# MCU.net
KiCad netlist of a schematic drawn in Altium Designer
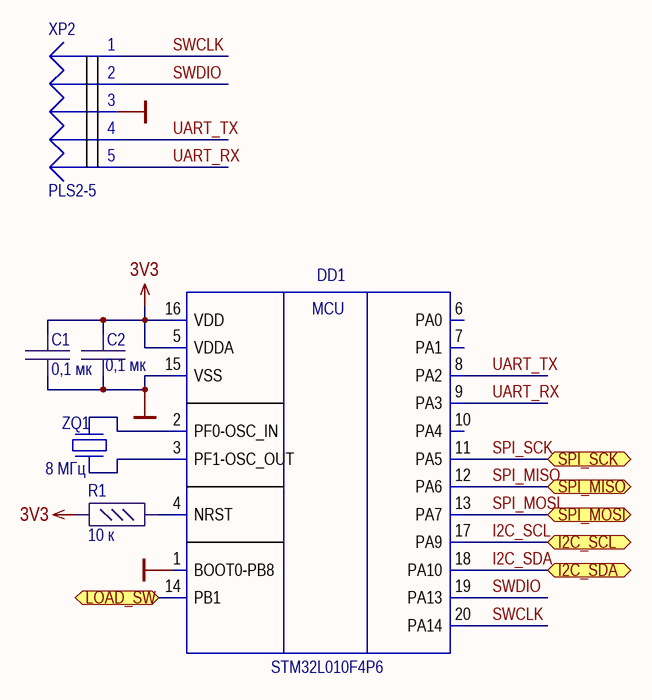
[diagram p0: MCU.SchDoc]

(export (version "E")
  (design (tool "Eeschema 10.0.6"))
  (components
    (comp (ref "C1")
      (value "0,1 мк")
      (footprint "C_0603")
      (description "CAP CER 0.1UF 100V X7R 0603")
      (fields
        (field (name "PART NUMBER") "GRM188R72A104MA35D")
        (field (name "MANUFACTURER") "Murata Electronics")
      )
      (libsource (lib "Database_Lib") (part "Capasitor"))
    )
    (comp (ref "C2")
      (value "0,1 мк")
      (footprint "C_0603")
      (description "CAP CER 0.1UF 100V X7R 0603")
      (fields
        (field (name "PART NUMBER") "GRM188R72A104MA35D")
        (field (name "MANUFACTURER") "Murata Electronics")
      )
      (libsource (lib "Database_Lib") (part "Capasitor"))
    )
    (comp (ref "DD1")
      (value "STM32L010F4P6")
      (footprint "TSSOP-20")
      (libsource (lib "6.Chips") (part "STM32L010F4P6"))
    )
    (comp (ref "R1")
      (value "10 к")
      (footprint "R_0603")
      (description "RES SMD 10K OHM 1% 1/10W 0603")
      (fields (field (name "PART NUMBER") "CR0603-FX-1002ELF") (field (name "MANUFACTURER") "Bourns Inc."))
      (libsource (lib "Database_Lib") (part "Resistor"))
    )
    (comp (ref "XP2") (value "PLS2-5") (footprint "PLS2-5") (libsource (lib "7.Connectors") (part "PLS2-5")))
    (comp (ref "ZQ1")
      (value "8 МГц")
      (footprint "MJ CRYSTAL")
      (libsource (lib "8.Resonarors") (part "NX5032GA-8MHz"))
    )
  )
  (nets
    (net (code "1") (name "/I2C_SCL") (class "Default")
      (node (ref "DD1") (pin "17") (pinfunction "PA9_17") (pintype "passive"))
    )
    (net (code "2") (name "/I2C_SDA") (class "Default")
      (node (ref "DD1") (pin "18") (pinfunction "PA10_18") (pintype "passive"))
    )
    (net (code "3") (name "/LOAD_SW") (class "Default")
      (node (ref "DD1") (pin "14") (pinfunction "PB1_14") (pintype "passive"))
    )
    (net (code "4") (name "/SPI_MISO") (class "Default")
      (node (ref "DD1") (pin "12") (pinfunction "PA6_12") (pintype "passive"))
    )
    (net (code "5") (name "/SPI_MOSI") (class "Default")
      (node (ref "DD1") (pin "13") (pinfunction "PA7_13") (pintype "passive"))
    )
    (net (code "6") (name "/SPI_SCK") (class "Default")
      (node (ref "DD1") (pin "11") (pinfunction "PA5_11") (pintype "passive"))
    )
    (net (code "7") (name "/SWCLK") (class "Default")
      (node (ref "DD1") (pin "20") (pinfunction "PA14_20") (pintype "passive"))
      (node (ref "XP2") (pin "1") (pinfunction "1_1") (pintype "passive"))
    )
    (net (code "8") (name "/SWDIO") (class "Default")
      (node (ref "DD1") (pin "19") (pinfunction "PA13_19") (pintype "passive"))
      (node (ref "XP2") (pin "2") (pinfunction "2_2") (pintype "passive"))
    )
    (net (code "9") (name "/UART_RX") (class "Default")
      (node (ref "DD1") (pin "9") (pinfunction "PA3_9") (pintype "passive"))
      (node (ref "XP2") (pin "5") (pinfunction "5_5") (pintype "passive"))
    )
    (net (code "10") (name "/UART_TX") (class "Default")
      (node (ref "DD1") (pin "8") (pinfunction "PA2_8") (pintype "passive"))
      (node (ref "XP2") (pin "4") (pinfunction "4_4") (pintype "passive"))
    )
    (net (code "11") (name "3V3") (class "Default")
      (node (ref "C1") (pin "2") (pinfunction "2_2") (pintype "passive"))
      (node (ref "C2") (pin "2") (pinfunction "2_2") (pintype "passive"))
      (node (ref "DD1") (pin "16") (pinfunction "VDD_16") (pintype "passive"))
      (node (ref "DD1") (pin "5") (pinfunction "VDDA_5") (pintype "passive"))
      (node (ref "R1") (pin "1") (pinfunction "1_1") (pintype "passive"))
    )
    (net (code "12") (name "GND") (class "Default")
      (node (ref "C1") (pin "1") (pinfunction "1_1") (pintype "passive"))
      (node (ref "C2") (pin "1") (pinfunction "1_1") (pintype "passive"))
      (node (ref "DD1") (pin "1") (pinfunction "BOOT0-PB8_1") (pintype "passive"))
      (node (ref "DD1") (pin "15") (pinfunction "VSS_15") (pintype "passive"))
      (node (ref "XP2") (pin "3") (pinfunction "3_3") (pintype "passive"))
    )
    (net (code "13") (name "Net-(DD1-NRST)") (class "Default")
      (node (ref "DD1") (pin "4") (pinfunction "NRST_4") (pintype "passive"))
      (node (ref "R1") (pin "2") (pinfunction "2_2") (pintype "passive"))
    )
    (net (code "14") (name "Net-(DD1-PF0-OSC_IN)") (class "Default")
      (node (ref "DD1") (pin "2") (pinfunction "PF0-OSC_IN_2") (pintype "passive"))
      (node (ref "ZQ1") (pin "3") (pinfunction "3_3") (pintype "passive"))
    )
    (net (code "15") (name "Net-(DD1-PF1-OSC_OUT)") (class "Default")
      (node (ref "DD1") (pin "3") (pinfunction "PF1-OSC_OUT_3") (pintype "passive"))
      (node (ref "ZQ1") (pin "1") (pinfunction "1_1") (pintype "passive"))
    )
    (net (code "16") (name "unconnected-(DD1-PA0-Pad6)") (class "Default")
      (node (ref "DD1") (pin "6") (pinfunction "PA0_6") (pintype "passive"))
    )
    (net (code "17") (name "unconnected-(DD1-PA1-Pad7)") (class "Default")
      (node (ref "DD1") (pin "7") (pinfunction "PA1_7") (pintype "passive"))
    )
    (net (code "18") (name "unconnected-(DD1-PA4-Pad10)") (class "Default")
      (node (ref "DD1") (pin "10") (pinfunction "PA4_10") (pintype "passive"))
    )
  )
)
